# OutputChannel.net
KiCad netlist of a schematic drawn in Altium Designer
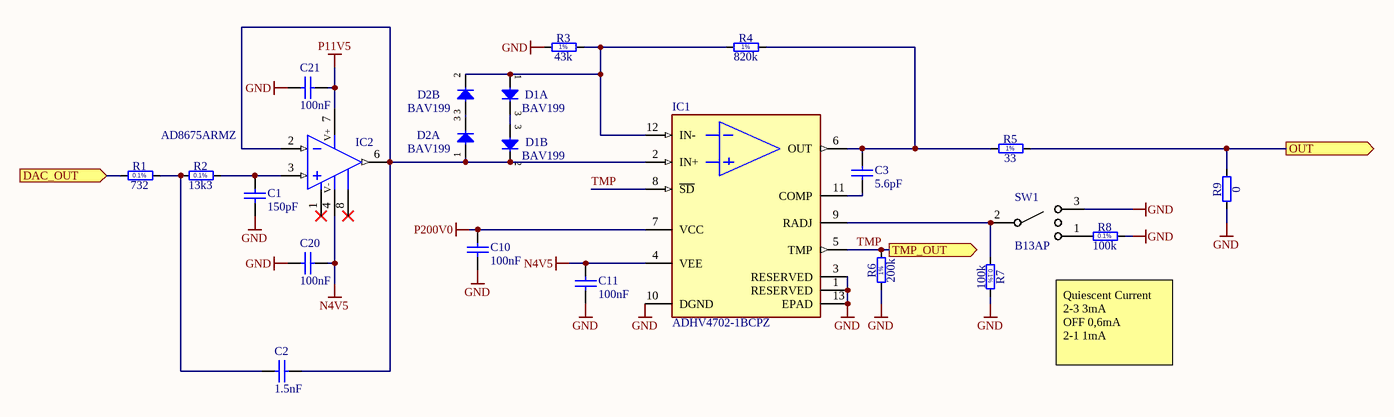
[diagram p0: OutputChannel.SchDoc]

(export (version "E")
  (design (tool "Eeschema 10.0.6"))
  (components
    (comp (ref "C1")
      (value "150pF")
      (footprint "C0402C151K4RACTU")
      (description "CAP CER 150PF 16V X7R 0402")
      (fields (field (name "TOLERANCE") "10%"))
      (libsource (lib "CapacitorLibrary") (part "C0402C151K4RACTU"))
    )
    (comp (ref "C2")
      (value "1.5nF")
      (footprint "C0402C152K3RACTU")
      (description "CAP CER 1,5nF 25V X7R 10% SMD 0402 125°C Paper T/R")
      (fields (field (name "TOLERANCE") "10%"))
      (libsource (lib "CapacitorLibrary") (part "C0402C152K3RACTU"))
    )
    (comp (ref "C3")
      (value "5.6pF")
      (footprint "CBR08C569CAGAC")
      (description "CAP CER 5.6PF 250V C0G/NP0 0805")
      (libsource (lib "CapacitorLibrary") (part "CBR08C569CAGAC"))
    )
    (comp (ref "C10")
      (value "100nF")
      (footprint "C2012X7T2E104K125AA")
      (fields (field (name "TOLERANCE") "10%"))
      (libsource (lib "CapacitorLibrary") (part "C2012X7T2E104K125AA"))
    )
    (comp (ref "C11")
      (value "100nF")
      (footprint "C0402C104K4RACTU")
      (description "Capacitor; Ceramic; Cap; .100uF; Tol 10%; SMT; Vol-Rtg 16V; X7R; Tape and Reel")
      (fields (field (name "TOLERANCE") "10%"))
      (libsource (lib "CapacitorLibrary") (part "C0402C104K4RACTU"))
    )
    (comp (ref "C20")
      (value "100nF")
      (footprint "C0402C104K4RACTU")
      (description "Capacitor; Ceramic; Cap; .100uF; Tol 10%; SMT; Vol-Rtg 16V; X7R; Tape and Reel")
      (fields (field (name "TOLERANCE") "10%"))
      (libsource (lib "CapacitorLibrary") (part "C0402C104K4RACTU"))
    )
    (comp (ref "C21")
      (value "100nF")
      (footprint "C0402C104K4RACTU")
      (description "Capacitor; Ceramic; Cap; .100uF; Tol 10%; SMT; Vol-Rtg 16V; X7R; Tape and Reel")
      (fields (field (name "TOLERANCE") "10%"))
      (libsource (lib "CapacitorLibrary") (part "C0402C104K4RACTU"))
    )
    (comp (ref "D1")
      (value "BAV199")
      (footprint "SOT95P240X110-3N")
      (description "Serial Diode")
      (fields
        (field (name "VOLTAGE") "75V")
        (field (name "POWER") "250mW")
        (field (name "AUTHOR") "CERN DEM JMW")
      )
      (libsource (lib "ICs And Semiconductors") (part "Diode x2 A1C3_A3C2"))
    )
    (comp (ref "D2")
      (value "BAV199")
      (footprint "SOT95P240X110-3N")
      (description "Serial Diode")
      (fields
        (field (name "VOLTAGE") "75V")
        (field (name "POWER") "250mW")
        (field (name "AUTHOR") "CERN DEM JMW")
      )
      (libsource (lib "ICs And Semiconductors") (part "Diode x2 A1C3_A3C2"))
    )
    (comp (ref "IC1")
      (value "ADHV4702-1BCPZ")
      (footprint "FP-ADHV4702-1BCPZ-IPC_B")
      (description "IC OPAMP GP 1 CIRCUIT 12LFCSP")
      (fields
        (field (name "OCTOPART") "https://octopart.com/adhv4702-1bcpz-analog+devices-95933827")
        (field (name "MANUFACTURER") "Analog Devices")
      )
      (libsource (lib "InzLib") (part "ADHV4702-1BCPZ"))
    )
    (comp (ref "IC2")
      (value "AD8675ARMZ")
      (footprint "SOP65P490X110-8N")
      (description "Operational Amplifier with Offset 1-8")
      (fields (field (name "MANUFACTURER") "ANALOG DEVICES") (field (name "AUTHOR") "CERN DEM JMW"))
      (libsource (lib "ICs And Semiconductors") (part "Operational Amplifier Type3"))
    )
    (comp (ref "R1")
      (value "732")
      (footprint "RESC1608X55N")
      (description "Resistor - 0.1%")
      (fields
        (field (name "PART NUMBER") "R0603_732R_0.1%_0.063W_10PPM")
        (field (name "POWER") "0.063W")
        (field (name "AUTHOR") "CERN DEM JLC")
      )
      (libsource (lib "Resistors") (part "Resistor - 0.1%"))
    )
    (comp (ref "R2")
      (value "13k3")
      (footprint "RESC1608X55N")
      (description "Resistor - 0.1%")
      (fields
        (field (name "PART NUMBER") "R0603_13K3_0.1%_0.063W_10PPM")
        (field (name "POWER") "0.063W")
        (field (name "AUTHOR") "CERN DEM JLC")
      )
      (libsource (lib "Resistors") (part "Resistor - 0.1%"))
    )
    (comp (ref "R3")
      (value "43k")
      (footprint "RESC1608X55N")
      (description "Resistor - 1%")
      (fields
        (field (name "PART NUMBER") "R0603_43K_1%_0.1W_100PPM")
        (field (name "POWER") "0.1W")
        (field (name "AUTHOR") "CERN DEM JLC")
      )
      (libsource (lib "Resistors") (part "Resistor - 1%"))
    )
    (comp (ref "R4")
      (value "820k")
      (footprint "RESC1608X55N")
      (description "Resistor - 1%")
      (fields
        (field (name "PART NUMBER") "R0603_820K_1%_0.1W_100PPM")
        (field (name "POWER") "0.1W")
        (field (name "AUTHOR") "CERN DEM JLC")
      )
      (libsource (lib "Resistors") (part "Resistor - 1%"))
    )
    (comp (ref "R5")
      (value "33")
      (footprint "RESC1608X55N")
      (description "Resistor - 1%")
      (fields
        (field (name "PART NUMBER") "R0603_33R_1%_0.1W_100PPM")
        (field (name "POWER") "0.1W")
        (field (name "AUTHOR") "CERN DEM JLC")
      )
      (libsource (lib "Resistors") (part "Resistor - 1%"))
    )
    (comp (ref "R6")
      (value "200k")
      (footprint "RESC1608X55N")
      (description "Resistor - 1%")
      (fields
        (field (name "PART NUMBER") "R0603_200K_1%_0.1W_100PPM")
        (field (name "POWER") "0.1W")
        (field (name "AUTHOR") "CERN DEM JLC")
      )
      (libsource (lib "Resistors") (part "Resistor - 1%"))
    )
    (comp (ref "R7")
      (value "100k")
      (footprint "RESC1608X55N")
      (description "Resistor - 0.1%")
      (fields
        (field (name "PART NUMBER") "R0603_100K_0.1%_0.063W_10PPM")
        (field (name "POWER") "0.063W")
        (field (name "AUTHOR") "CERN DEM JLC")
      )
      (libsource (lib "Resistors") (part "Resistor - 0.1%"))
    )
    (comp (ref "R8")
      (value "100k")
      (footprint "RESC1608X55N")
      (description "Resistor - 0.1%")
      (fields
        (field (name "PART NUMBER") "R0603_100K_0.1%_0.063W_10PPM")
        (field (name "POWER") "0.063W")
        (field (name "AUTHOR") "CERN DEM JLC")
      )
      (libsource (lib "Resistors") (part "Resistor - 0.1%"))
    )
    (comp (ref "R9")
      (value "0")
      (footprint "RESC1608X55N")
      (description "Resistor")
      (fields
        (field (name "PART NUMBER") "R0603_0R_JUMPER")
        (field (name "MANUFACTURER") "GENERIC")
        (field (name "AUTHOR") "CERN DEM JLC")
      )
      (libsource (lib "Resistors") (part "Resistor"))
    )
    (comp (ref "SW1")
      (value "B13AP")
      (footprint "B13AP")
      (description "Switch;  Sealed;  Anti-Static Toggle;  SPDT;  ON-OFF-ON;  Str PC;  No Cap;  0.4A;  28VAC/DC")
      (libsource (lib "InzLib") (part "B13AP"))
    )
  )
  (nets
    (net (code "1") (name "/DAC_OUT") (class "Default")
      (node (ref "R1") (pin "1") (pinfunction "1_1") (pintype "passive"))
    )
    (net (code "2") (name "/OUT") (class "Default")
      (node (ref "R5") (pin "2") (pinfunction "2_2") (pintype "passive"))
      (node (ref "R9") (pin "2") (pinfunction "2_2") (pintype "passive"))
    )
    (net (code "3") (name "/TMP") (class "Default")
      (node (ref "IC1") (pin "5") (pinfunction "TMP_5") (pintype "output"))
      (node (ref "IC1") (pin "8") (pinfunction "~{SD}_8") (pintype "input"))
      (node (ref "R6") (pin "2") (pinfunction "2_2") (pintype "passive"))
    )
    (net (code "4") (name "GND") (class "Default")
      (node (ref "C1") (pin "1") (pinfunction "1_1") (pintype "passive"))
      (node (ref "C10") (pin "1") (pinfunction "1_1") (pintype "passive"))
      (node (ref "C11") (pin "1") (pinfunction "1_1") (pintype "passive"))
      (node (ref "C20") (pin "2") (pinfunction "2_2") (pintype "passive"))
      (node (ref "C21") (pin "2") (pinfunction "2_2") (pintype "passive"))
      (node (ref "IC1") (pin "1") (pinfunction "RESERVED_1") (pintype "passive"))
      (node (ref "IC1") (pin "10") (pinfunction "DGND_10") (pintype "open_emitter"))
      (node (ref "IC1") (pin "13") (pinfunction "EPAD_13") (pintype "passive"))
      (node (ref "IC1") (pin "3") (pinfunction "RESERVED_3") (pintype "passive"))
      (node (ref "R3") (pin "1") (pinfunction "1_1") (pintype "passive"))
      (node (ref "R6") (pin "1") (pinfunction "1_1") (pintype "passive"))
      (node (ref "R7") (pin "2") (pinfunction "2_2") (pintype "passive"))
      (node (ref "R8") (pin "2") (pinfunction "2_2") (pintype "passive"))
      (node (ref "R9") (pin "1") (pinfunction "1_1") (pintype "passive"))
      (node (ref "SW1") (pin "3") (pinfunction "NC_3") (pintype "passive"))
    )
    (net (code "5") (name "N4V5") (class "Default")
      (node (ref "C11") (pin "2") (pinfunction "2_2") (pintype "passive"))
      (node (ref "C20") (pin "1") (pinfunction "1_1") (pintype "passive"))
      (node (ref "IC1") (pin "4") (pinfunction "VEE_4") (pintype "power_in"))
      (node (ref "IC2") (pin "4") (pinfunction "V-_4") (pintype "power_in"))
    )
    (net (code "6") (name "Net-(C2-Pad1)") (class "Default")
      (node (ref "C2") (pin "1") (pinfunction "1_1") (pintype "passive"))
      (node (ref "R1") (pin "2") (pinfunction "2_2") (pintype "passive"))
      (node (ref "R2") (pin "1") (pinfunction "1_1") (pintype "passive"))
    )
    (net (code "7") (name "Net-(D1A-A)") (class "Default")
      (node (ref "D1") (pin "1") (pinfunction "A_1") (pintype "passive"))
      (node (ref "D2") (pin "2") (pinfunction "C_2") (pintype "passive"))
      (node (ref "IC1") (pin "12") (pinfunction "IN-_12") (pintype "input"))
      (node (ref "R3") (pin "2") (pinfunction "2_2") (pintype "passive"))
      (node (ref "R4") (pin "1") (pinfunction "1_1") (pintype "passive"))
    )
    (net (code "8") (name "Net-(D1A-COMAC)") (class "Default")
      (node (ref "D1") (pin "3") (pinfunction "COMAC_3") (pintype "passive"))
    )
    (net (code "9") (name "Net-(D1B-C)") (class "Default")
      (node (ref "C2") (pin "2") (pinfunction "2_2") (pintype "passive"))
      (node (ref "D1") (pin "2") (pinfunction "C_2") (pintype "passive"))
      (node (ref "D2") (pin "1") (pinfunction "A_1") (pintype "passive"))
      (node (ref "IC1") (pin "2") (pinfunction "IN+_2") (pintype "input"))
      (node (ref "IC2") (pin "2") (pinfunction "IN-_2") (pintype "input"))
      (node (ref "IC2") (pin "6") (pinfunction "OUT_6") (pintype "output"))
    )
    (net (code "10") (name "Net-(D2A-COMAC)") (class "Default")
      (node (ref "D2") (pin "3") (pinfunction "COMAC_3") (pintype "passive"))
    )
    (net (code "11") (name "Net-(IC1-COMP)") (class "Default")
      (node (ref "C3") (pin "1") (pinfunction "1_1") (pintype "passive"))
      (node (ref "IC1") (pin "11") (pinfunction "COMP_11") (pintype "passive"))
    )
    (net (code "12") (name "Net-(IC1-OUT)") (class "Default")
      (node (ref "C3") (pin "2") (pinfunction "2_2") (pintype "passive"))
      (node (ref "IC1") (pin "6") (pinfunction "OUT_6") (pintype "output"))
      (node (ref "R4") (pin "2") (pinfunction "2_2") (pintype "passive"))
      (node (ref "R5") (pin "1") (pinfunction "1_1") (pintype "passive"))
    )
    (net (code "13") (name "Net-(IC1-RADJ)") (class "Default")
      (node (ref "IC1") (pin "9") (pinfunction "RADJ_9") (pintype "passive"))
      (node (ref "R7") (pin "1") (pinfunction "1_1") (pintype "passive"))
      (node (ref "SW1") (pin "2") (pinfunction "C_2") (pintype "passive"))
    )
    (net (code "14") (name "Net-(IC2-IN+)") (class "Default")
      (node (ref "C1") (pin "2") (pinfunction "2_2") (pintype "passive"))
      (node (ref "IC2") (pin "3") (pinfunction "IN+_3") (pintype "input"))
      (node (ref "R2") (pin "2") (pinfunction "2_2") (pintype "passive"))
    )
    (net (code "15") (name "Net-(SW1-NO)") (class "Default")
      (node (ref "R8") (pin "1") (pinfunction "1_1") (pintype "passive"))
      (node (ref "SW1") (pin "1") (pinfunction "NO_1") (pintype "passive"))
    )
    (net (code "16") (name "P11V5") (class "Default")
      (node (ref "C21") (pin "1") (pinfunction "1_1") (pintype "passive"))
      (node (ref "IC2") (pin "7") (pinfunction "V+_7") (pintype "power_in"))
    )
    (net (code "17") (name "P200V0") (class "Default")
      (node (ref "C10") (pin "2") (pinfunction "2_2") (pintype "passive"))
      (node (ref "IC1") (pin "7") (pinfunction "VCC_7") (pintype "power_in"))
    )
    (net (code "18") (name "unconnected-(IC2-OFFSET-Pad1)") (class "Default")
      (node (ref "IC2") (pin "1") (pinfunction "OFFSET_1") (pintype "passive+no_connect"))
    )
    (net (code "19") (name "unconnected-(IC2-OFFSET-Pad8)") (class "Default")
      (node (ref "IC2") (pin "8") (pinfunction "OFFSET_8") (pintype "passive+no_connect"))
    )
  )
)
